# czujniki.net
KiCad netlist of a schematic drawn in EAGLE
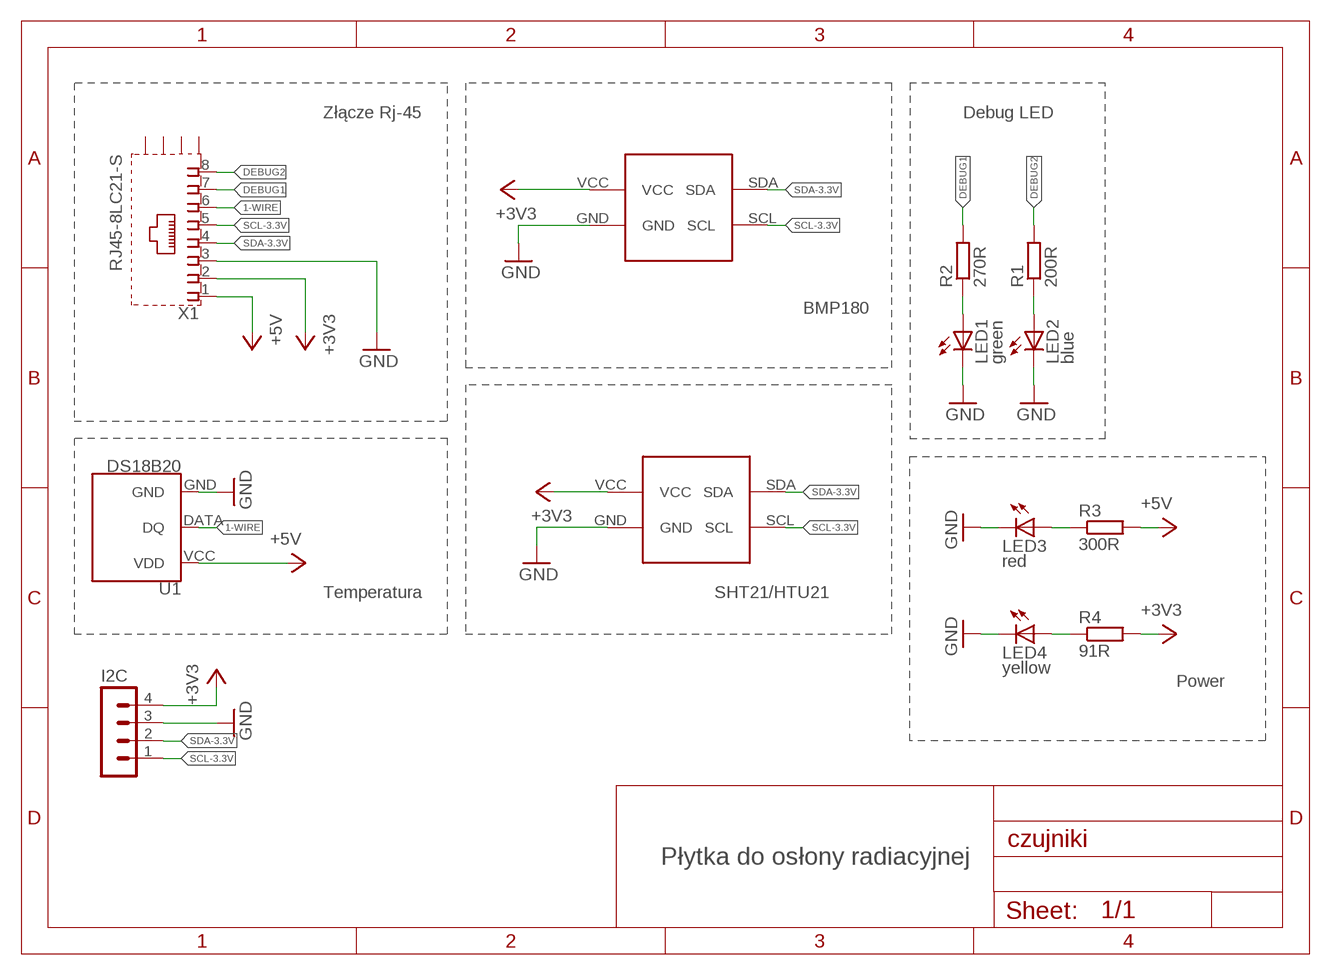
[diagram p0: schematic, sheet 1]

(export (version "E")
  (design (tool "Eeschema 10.0.6"))
  (components
    (comp (ref "I2C")
      (value "MA04-1")
      (footprint "eagle-import:MA04-1")
      (libsource (lib "eagle-import") (part "MA04-1"))
    )
    (comp (ref "LED1")
      (value "green")
      (footprint "eagle-import:CHIPLED_1206")
      (libsource (lib "eagle-import") (part "LEDCHIPLED_1206"))
    )
    (comp (ref "LED2")
      (value "blue")
      (footprint "eagle-import:CHIPLED_1206")
      (libsource (lib "eagle-import") (part "LEDCHIPLED_1206"))
    )
    (comp (ref "LED3")
      (value "red")
      (footprint "eagle-import:CHIPLED_1206")
      (libsource (lib "eagle-import") (part "LEDCHIPLED_1206"))
    )
    (comp (ref "LED4")
      (value "yellow")
      (footprint "eagle-import:CHIPLED_1206")
      (libsource (lib "eagle-import") (part "LEDCHIPLED_1206"))
    )
    (comp (ref "R1")
      (value "200R")
      (footprint "eagle-import:M0805")
      (libsource (lib "eagle-import") (part "R-EU_M0805"))
    )
    (comp (ref "R2")
      (value "270R")
      (footprint "eagle-import:M0805")
      (libsource (lib "eagle-import") (part "R-EU_M0805"))
    )
    (comp (ref "R3")
      (value "300R")
      (footprint "eagle-import:M0805")
      (libsource (lib "eagle-import") (part "R-EU_M0805"))
    )
    (comp (ref "R4")
      (value "91R")
      (footprint "eagle-import:M0805")
      (libsource (lib "eagle-import") (part "R-EU_M0805"))
    )
    (comp (ref "U$1")
      (value "BMP180")
      (footprint "eagle-import:BMP180")
      (libsource (lib "eagle-import") (part "BMP180"))
    )
    (comp (ref "U$2")
      (value "I2C_BOARD")
      (footprint "eagle-import:I2C_BOARD")
      (libsource (lib "eagle-import") (part "I2C_BOARD"))
    )
    (comp (ref "U1")
      (value "DS18B20")
      (footprint "eagle-import:TO-92-AMMO")
      (libsource (lib "eagle-import") (part "DS18B20"))
    )
    (comp (ref "X1")
      (value "RJ45-8LC21-S")
      (footprint "eagle-import:RJ45-SHIELD1")
      (libsource (lib "eagle-import") (part "RJ4521-S-8LC"))
    )
  )
  (nets
    (net (code "1") (name "+3V3") (class "Default")
      (node (ref "I2C") (pin "4") (pinfunction "4_4") (pintype "passive"))
      (node (ref "R4") (pin "2") (pinfunction "2_2") (pintype "passive"))
      (node (ref "U$1") (pin "VCC") (pinfunction "VCC_VCC") (pintype "bidirectional"))
      (node (ref "U$2") (pin "VCC") (pinfunction "VCC_VCC") (pintype "bidirectional"))
      (node (ref "X1") (pin "2") (pinfunction "2_2") (pintype "passive"))
    )
    (net (code "2") (name "+5V") (class "Default")
      (node (ref "R3") (pin "2") (pinfunction "2_2") (pintype "passive"))
      (node (ref "U1") (pin "VCC") (pinfunction "VDD_VCC") (pintype "power_in"))
      (node (ref "X1") (pin "1") (pinfunction "1_1") (pintype "passive"))
    )
    (net (code "3") (name "1-WIRE") (class "Default")
      (node (ref "U1") (pin "DATA") (pinfunction "DQ_DATA") (pintype "bidirectional"))
      (node (ref "X1") (pin "6") (pinfunction "6_6") (pintype "passive"))
    )
    (net (code "4") (name "DEBUG1") (class "Default")
      (node (ref "R2") (pin "2") (pinfunction "2_2") (pintype "passive"))
      (node (ref "X1") (pin "7") (pinfunction "7_7") (pintype "passive"))
    )
    (net (code "5") (name "DEBUG2") (class "Default")
      (node (ref "R1") (pin "2") (pinfunction "2_2") (pintype "passive"))
      (node (ref "X1") (pin "8") (pinfunction "8_8") (pintype "passive"))
    )
    (net (code "6") (name "GND") (class "Default")
      (node (ref "I2C") (pin "3") (pinfunction "3_3") (pintype "passive"))
      (node (ref "LED1") (pin "C") (pinfunction "C_C") (pintype "passive"))
      (node (ref "LED2") (pin "C") (pinfunction "C_C") (pintype "passive"))
      (node (ref "LED3") (pin "C") (pinfunction "C_C") (pintype "passive"))
      (node (ref "LED4") (pin "C") (pinfunction "C_C") (pintype "passive"))
      (node (ref "U$1") (pin "GND") (pinfunction "GND_GND") (pintype "bidirectional"))
      (node (ref "U$2") (pin "GND") (pinfunction "GND_GND") (pintype "bidirectional"))
      (node (ref "U1") (pin "GND") (pinfunction "GND_GND") (pintype "power_in"))
      (node (ref "X1") (pin "3") (pinfunction "3_3") (pintype "passive"))
    )
    (net (code "7") (name "Net-(LED1-PadA)") (class "Default")
      (node (ref "LED1") (pin "A") (pinfunction "A_A") (pintype "passive"))
      (node (ref "R2") (pin "1") (pinfunction "1_1") (pintype "passive"))
    )
    (net (code "8") (name "Net-(LED2-PadA)") (class "Default")
      (node (ref "LED2") (pin "A") (pinfunction "A_A") (pintype "passive"))
      (node (ref "R1") (pin "1") (pinfunction "1_1") (pintype "passive"))
    )
    (net (code "9") (name "Net-(LED3-PadA)") (class "Default")
      (node (ref "LED3") (pin "A") (pinfunction "A_A") (pintype "passive"))
      (node (ref "R3") (pin "1") (pinfunction "1_1") (pintype "passive"))
    )
    (net (code "10") (name "Net-(LED4-PadA)") (class "Default")
      (node (ref "LED4") (pin "A") (pinfunction "A_A") (pintype "passive"))
      (node (ref "R4") (pin "1") (pinfunction "1_1") (pintype "passive"))
    )
    (net (code "11") (name "SCL-3.3V") (class "Default")
      (node (ref "I2C") (pin "1") (pinfunction "1_1") (pintype "passive"))
      (node (ref "U$1") (pin "SCL") (pinfunction "SCL_SCL") (pintype "bidirectional"))
      (node (ref "U$2") (pin "SCL") (pinfunction "SCL_SCL") (pintype "bidirectional"))
      (node (ref "X1") (pin "5") (pinfunction "5_5") (pintype "passive"))
    )
    (net (code "12") (name "SDA-3.3V") (class "Default")
      (node (ref "I2C") (pin "2") (pinfunction "2_2") (pintype "passive"))
      (node (ref "U$1") (pin "SDA") (pinfunction "SDA_SDA") (pintype "bidirectional"))
      (node (ref "U$2") (pin "SDA") (pinfunction "SDA_SDA") (pintype "bidirectional"))
      (node (ref "X1") (pin "4") (pinfunction "4_4") (pintype "passive"))
    )
    (net (code "13") (name "unconnected-(X1-S-PadS1)") (class "Default")
      (node (ref "X1") (pin "S1") (pinfunction "S_S1") (pintype "passive"))
    )
    (net (code "14") (name "unconnected-(X1-S-PadS2)") (class "Default")
      (node (ref "X1") (pin "S2") (pinfunction "S_S2") (pintype "passive"))
    )
    (net (code "15") (name "unconnected-(X1-S-PadS3)") (class "Default")
      (node (ref "X1") (pin "S3") (pinfunction "S_S3") (pintype "passive"))
    )
    (net (code "16") (name "unconnected-(X1-S-PadS4)") (class "Default")
      (node (ref "X1") (pin "S4") (pinfunction "S_S4") (pintype "passive"))
    )
  )
)
